# 3PDT.net
KiCad netlist of a schematic drawn in Altium Designer
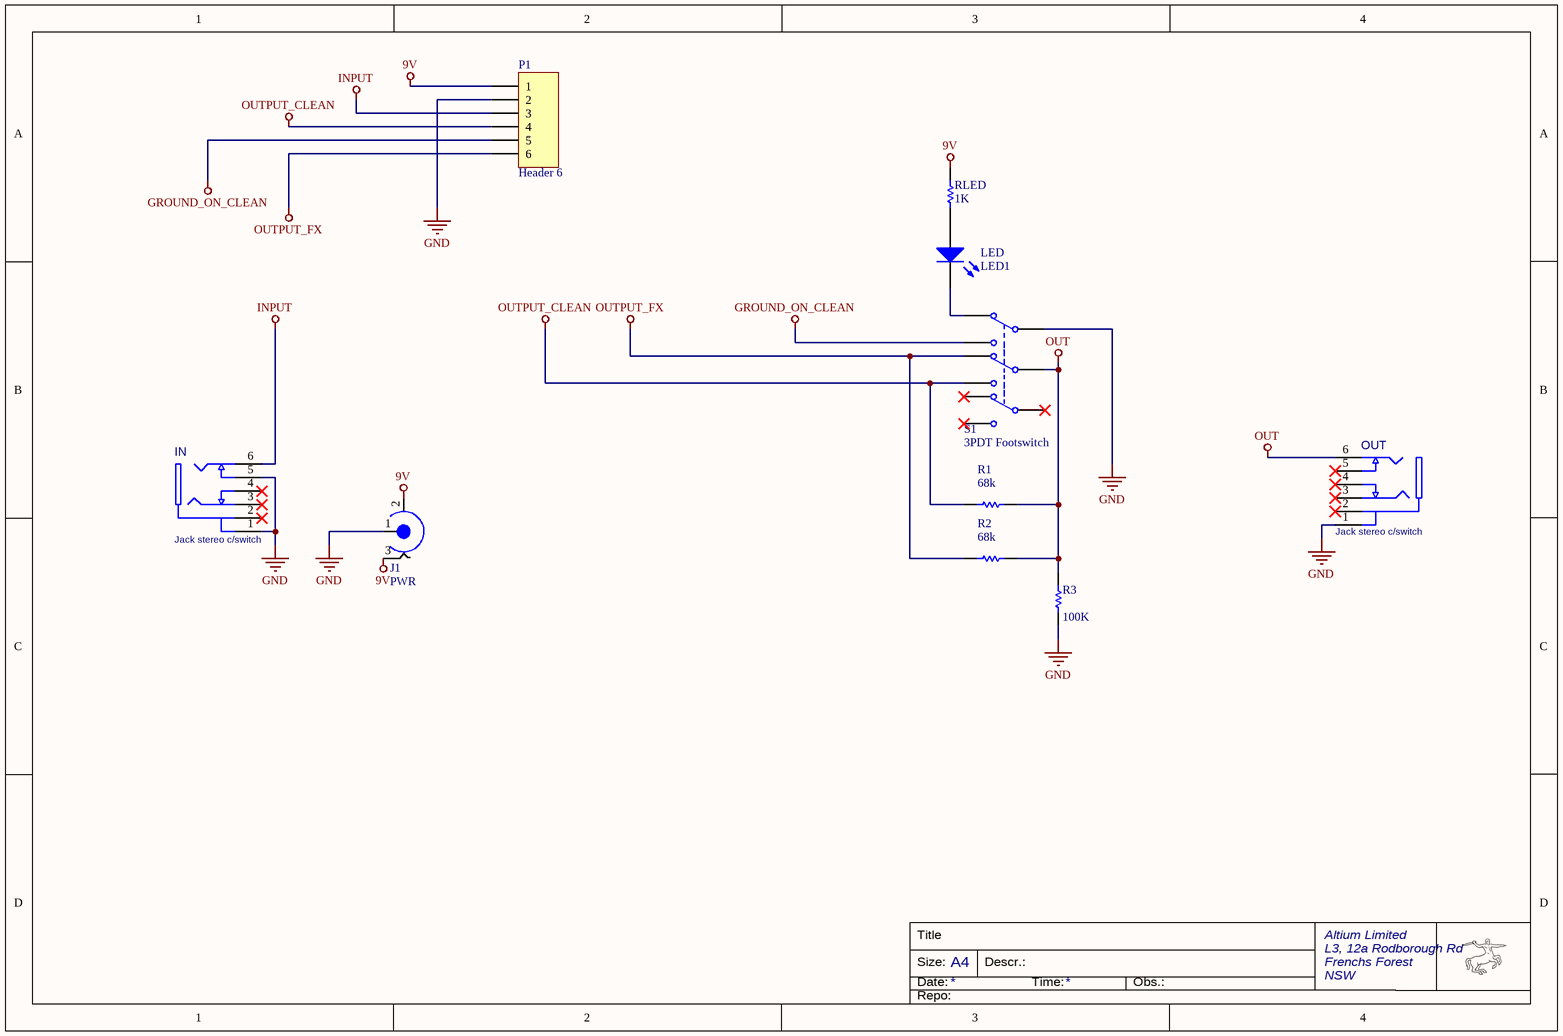
[diagram p0: 3PDT.SchDoc]

(export (version "E")
  (design (tool "Eeschema 10.0.6"))
  (components
    (comp (ref "IN")
      (value "Jack stereo c/switch")
      (footprint "NMJ6HCD2")
      (description "Jack 1/4\" Stereo Switched")
      (fields (field (name "MF") "Neutrik"))
      (libsource (lib "neutrik") (part "NMJ6HCD2"))
    )
    (comp (ref "J1")
      (value "PWR")
      (footprint "Power Connector Round Pads")
      (libsource (lib "StompboxesLibs") (part "Power Connector"))
    )
    (comp (ref "LED")
      (value "LED1")
      (footprint "LED")
      (description "Typical RED GaAs LED")
      (fields (field (name "PUBLISHER") "Altium Limited"))
      (libsource (lib "Miscellaneous Devices") (part "LED1"))
    )
    (comp (ref "OUT")
      (value "Jack stereo c/switch")
      (footprint "NMJ6HCD2")
      (description "Jack 1/4\" Stereo Switched")
      (fields (field (name "MF") "Neutrik"))
      (libsource (lib "neutrik") (part "NMJ6HCD2"))
    )
    (comp (ref "P1")
      (value "Header 6")
      (footprint "Header 6")
      (description "Header, 6-Pin")
      (fields (field (name "PUBLISHER") "Altium Limited"))
      (libsource (lib "Miscellaneous Connectors") (part "Header 6"))
    )
    (comp (ref "R1")
      (value "68k")
      (footprint "Res 0.2")
      (description "Resistor")
      (fields (field (name "Comment") "Res1") (field (name "PUBLISHER") "Altium Limited"))
      (libsource (lib "Miscellaneous Devices") (part "Res1"))
    )
    (comp (ref "R2")
      (value "68k")
      (footprint "Res 0.2")
      (description "Resistor")
      (fields (field (name "Comment") "Res1") (field (name "PUBLISHER") "Altium Limited"))
      (libsource (lib "Miscellaneous Devices") (part "Res1"))
    )
    (comp (ref "R3")
      (value "100K")
      (footprint "Res 0.2")
      (description "Resistor")
      (fields (field (name "Comment") "Res1") (field (name "PUBLISHER") "Altium Limited"))
      (libsource (lib "Miscellaneous Devices") (part "Res1"))
    )
    (comp (ref "RLED")
      (value "1K")
      (footprint "Res 0.2")
      (description "Resistor")
      (fields (field (name "Comment") "Res1") (field (name "PUBLISHER") "Altium Limited"))
      (libsource (lib "Miscellaneous Devices") (part "Res1"))
    )
    (comp (ref "S1")
      (value "3PDT Footswitch")
      (footprint "3PDT FOOTSWITCH")
      (libsource (lib "StompboxesLibs") (part "3PDT Footswitch"))
    )
  )
  (nets
    (net (code "1") (name "9V") (class "Default")
      (node (ref "J1") (pin "2") (pinfunction "2_2") (pintype "passive"))
      (node (ref "J1") (pin "3") (pinfunction "3_3") (pintype "passive"))
      (node (ref "P1") (pin "1") (pinfunction "1_1") (pintype "passive"))
      (node (ref "RLED") (pin "2") (pinfunction "2_2") (pintype "passive"))
    )
    (net (code "2") (name "GND") (class "Default")
      (node (ref "IN") (pin "1") (pinfunction "1_1") (pintype "power_in"))
      (node (ref "IN") (pin "5") (pinfunction "5_5") (pintype "power_in"))
      (node (ref "J1") (pin "1") (pinfunction "1_1") (pintype "passive"))
      (node (ref "OUT") (pin "1") (pinfunction "1_1") (pintype "power_in"))
      (node (ref "P1") (pin "2") (pinfunction "2_2") (pintype "passive"))
      (node (ref "R3") (pin "1") (pinfunction "1_1") (pintype "passive"))
      (node (ref "S1") (pin "2a") (pinfunction "COMMON1_2a") (pintype "passive"))
    )
    (net (code "3") (name "GROUND_ON_CLEAN") (class "Default")
      (node (ref "P1") (pin "5") (pinfunction "5_5") (pintype "passive"))
      (node (ref "S1") (pin "3a") (pinfunction "NO1_3a") (pintype "passive"))
    )
    (net (code "4") (name "INPUT") (class "Default")
      (node (ref "IN") (pin "6") (pinfunction "6_6") (pintype "power_in"))
      (node (ref "P1") (pin "3") (pinfunction "3_3") (pintype "passive"))
    )
    (net (code "5") (name "Net-(LED-A)") (class "Default")
      (node (ref "LED") (pin "1") (pinfunction "A_1") (pintype "passive"))
      (node (ref "RLED") (pin "1") (pinfunction "1_1") (pintype "passive"))
    )
    (net (code "6") (name "Net-(LED-K)") (class "Default")
      (node (ref "LED") (pin "2") (pinfunction "K_2") (pintype "passive"))
      (node (ref "S1") (pin "1a") (pinfunction "NC1_1a") (pintype "passive"))
    )
    (net (code "7") (name "OUT") (class "Default")
      (node (ref "OUT") (pin "6") (pinfunction "6_6") (pintype "power_in"))
      (node (ref "R1") (pin "1") (pinfunction "1_1") (pintype "passive"))
      (node (ref "R2") (pin "1") (pinfunction "1_1") (pintype "passive"))
      (node (ref "R3") (pin "2") (pinfunction "2_2") (pintype "passive"))
      (node (ref "S1") (pin "2b") (pinfunction "COMMON2_2b") (pintype "passive"))
    )
    (net (code "8") (name "OUTPUT_CLEAN") (class "Default")
      (node (ref "P1") (pin "4") (pinfunction "4_4") (pintype "passive"))
      (node (ref "R1") (pin "2") (pinfunction "2_2") (pintype "passive"))
      (node (ref "S1") (pin "3b") (pinfunction "NO2_3b") (pintype "passive"))
    )
    (net (code "9") (name "OUTPUT_FX") (class "Default")
      (node (ref "P1") (pin "6") (pinfunction "6_6") (pintype "passive"))
      (node (ref "R2") (pin "2") (pinfunction "2_2") (pintype "passive"))
      (node (ref "S1") (pin "1b") (pinfunction "NC2_1b") (pintype "passive"))
    )
    (net (code "10") (name "unconnected-(IN-Pad2)") (class "Default")
      (node (ref "IN") (pin "2") (pinfunction "2_2") (pintype "power_in+no_connect"))
    )
    (net (code "11") (name "unconnected-(IN-Pad3)") (class "Default")
      (node (ref "IN") (pin "3") (pinfunction "3_3") (pintype "power_in+no_connect"))
    )
    (net (code "12") (name "unconnected-(IN-Pad4)") (class "Default")
      (node (ref "IN") (pin "4") (pinfunction "4_4") (pintype "power_in+no_connect"))
    )
    (net (code "13") (name "unconnected-(OUT-Pad2)") (class "Default")
      (node (ref "OUT") (pin "2") (pinfunction "2_2") (pintype "power_in+no_connect"))
    )
    (net (code "14") (name "unconnected-(OUT-Pad3)") (class "Default")
      (node (ref "OUT") (pin "3") (pinfunction "3_3") (pintype "power_in+no_connect"))
    )
    (net (code "15") (name "unconnected-(OUT-Pad4)") (class "Default")
      (node (ref "OUT") (pin "4") (pinfunction "4_4") (pintype "power_in+no_connect"))
    )
    (net (code "16") (name "unconnected-(OUT-Pad5)") (class "Default")
      (node (ref "OUT") (pin "5") (pinfunction "5_5") (pintype "power_in+no_connect"))
    )
    (net (code "17") (name "unconnected-(S1-COMMON3-Pad2c)") (class "Default")
      (node (ref "S1") (pin "2c") (pinfunction "COMMON3_2c") (pintype "passive+no_connect"))
    )
    (net (code "18") (name "unconnected-(S1-NC3-Pad1c)") (class "Default")
      (node (ref "S1") (pin "1c") (pinfunction "NC3_1c") (pintype "passive+no_connect"))
    )
    (net (code "19") (name "unconnected-(S1-NO3-Pad3c)") (class "Default")
      (node (ref "S1") (pin "3c") (pinfunction "NO3_3c") (pintype "passive+no_connect"))
    )
  )
)
